# HB-OU-MP3-LED_V1_3.net
KiCad netlist of a schematic drawn in EAGLE
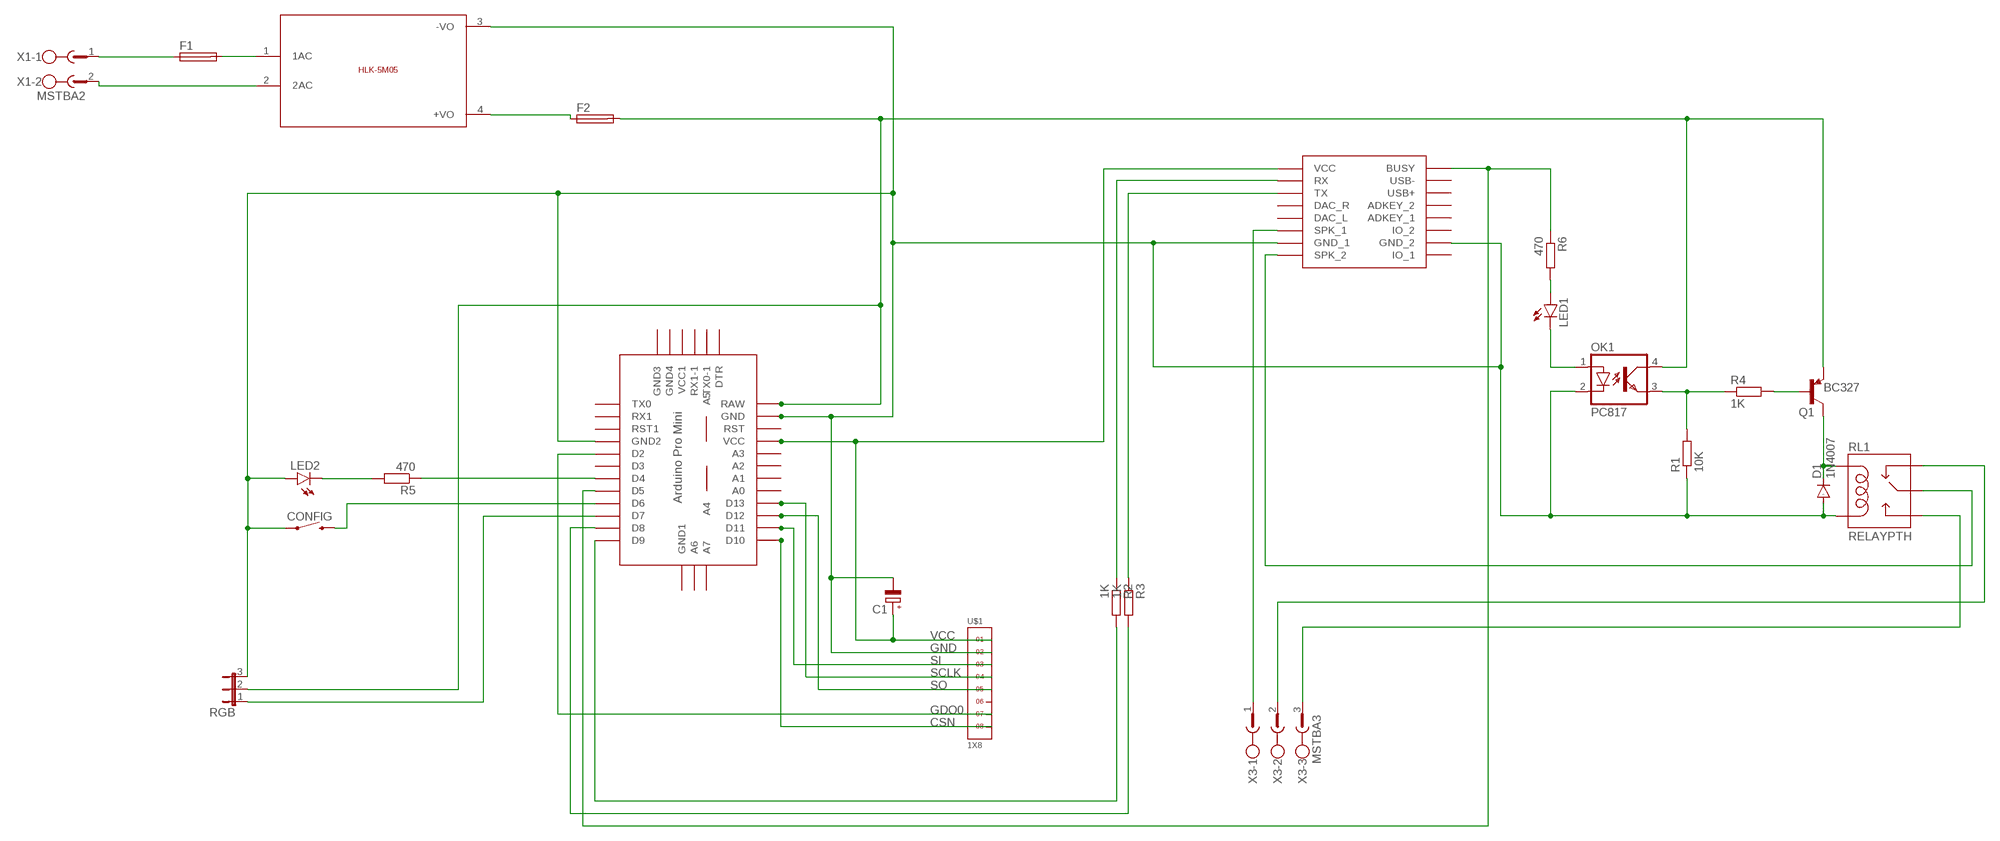
[diagram p0: schematic, sheet 1]

(export (version "E")
  (design (tool "Eeschema 10.0.6"))
  (components
    (comp (ref "C1")
      (value "CPOL-EUE2.5-5")
      (footprint "eagle-import:E2,5-5")
      (libsource (lib "eagle-import") (part "CPOL-EUE2.5-5"))
    )
    (comp (ref "CONFIG")
      (value "MOMENTARY-SWITCH-SPST-PTH-6.0MM-KIT")
      (footprint "eagle-import:TACTILE_SWITCH_PTH_6.0MM_KIT")
      (libsource (lib "eagle-import") (part "MOMENTARY-SWITCH-SPST-PTH-6.0MM-KIT"))
    )
    (comp (ref "D1")
      (value "1N4007")
      (footprint "eagle-import:DO41-10")
      (libsource (lib "eagle-import") (part "1N4004"))
    )
    (comp (ref "F1")
      (value "SH22,5A")
      (footprint "eagle-import:SH22,5A")
      (fields (field (name "MPN") "0031.7701.11"))
      (libsource (lib "eagle-import") (part "SH22,5A"))
    )
    (comp (ref "F2")
      (value "SH22,5A")
      (footprint "eagle-import:SH22,5A")
      (fields (field (name "MPN") "0031.7701.11"))
      (libsource (lib "eagle-import") (part "SH22,5A"))
    )
    (comp (ref "LED1")
      (value "LED3MM")
      (footprint "eagle-import:LED3MM")
      (libsource (lib "eagle-import") (part "LED3MM"))
    )
    (comp (ref "LED2")
      (value "LED3MM")
      (footprint "eagle-import:LED3MM")
      (libsource (lib "eagle-import") (part "LED3MM"))
    )
    (comp (ref "OK1")
      (value "PC817")
      (footprint "eagle-import:DIL04")
      (fields (field (name "MPN") "PC817X4J000F"))
      (libsource (lib "eagle-import") (part "PC817"))
    )
    (comp (ref "Q1")
      (value "BC327")
      (footprint "eagle-import:TO92")
      (libsource (lib "eagle-import") (part "BC327"))
    )
    (comp (ref "R1")
      (value "10K")
      (footprint "eagle-import:0309_10")
      (libsource (lib "eagle-import") (part "R-EU_0309/10"))
    )
    (comp (ref "R2")
      (value "1K")
      (footprint "eagle-import:0309_10")
      (libsource (lib "eagle-import") (part "R-EU_0309/10"))
    )
    (comp (ref "R3")
      (value "1K")
      (footprint "eagle-import:0309_10")
      (libsource (lib "eagle-import") (part "R-EU_0309/10"))
    )
    (comp (ref "R4")
      (value "1K")
      (footprint "eagle-import:0309_10")
      (libsource (lib "eagle-import") (part "R-EU_0309/10"))
    )
    (comp (ref "R5")
      (value "470")
      (footprint "eagle-import:0309_10")
      (libsource (lib "eagle-import") (part "R-EU_0309/10"))
    )
    (comp (ref "R6")
      (value "470")
      (footprint "eagle-import:0309_10")
      (libsource (lib "eagle-import") (part "R-EU_0309/10"))
    )
    (comp (ref "RGB")
      (value "JP2E")
      (footprint "eagle-import:JP2")
      (libsource (lib "eagle-import") (part "JP2E"))
    )
    (comp (ref "RL1")
      (value "RELAYPTH")
      (footprint "eagle-import:SRD-05VDC-SL-C")
      (libsource (lib "eagle-import") (part "RELAYPTH"))
    )
    (comp (ref "U$1")
      (value "1X8")
      (footprint "eagle-import:1X8")
      (libsource (lib "eagle-import") (part "1X8"))
    )
    (comp (ref "U$2")
      (value "ABK-PRO-MINI")
      (footprint "eagle-import:ABK-PRO-MINI")
      (libsource (lib "eagle-import") (part "ABK-PRO-MINI"))
    )
    (comp (ref "U$3")
      (value "5VDC/5W")
      (footprint "eagle-import:HLK-5M05")
      (libsource (lib "eagle-import") (part "HLK-5M05"))
    )
    (comp (ref "U$4")
      (value "DFPLAYER")
      (footprint "eagle-import:DFPLAYER")
      (libsource (lib "eagle-import") (part "DFPLAYER"))
    )
    (comp (ref "X1")
      (value "MSTBA2")
      (footprint "eagle-import:MSTBA2")
      (fields (field (name "MF") "FARNELL") (field (name "MPN") "1757242"))
      (libsource (lib "eagle-import") (part "MSTBA2"))
    )
    (comp (ref "X3")
      (value "MSTBA3")
      (footprint "eagle-import:MSTBA3")
      (fields (field (name "MF") "FARNELL") (field (name "MPN") "1757255"))
      (libsource (lib "eagle-import") (part "MSTBA3"))
    )
  )
  (nets
    (net (code "1") (name "/CSN") (class "Default")
      (node (ref "U$1") (pin "8") (pinfunction "8_8") (pintype "bidirectional"))
      (node (ref "U$2") (pin "D10") (pinfunction "D10_D10") (pintype "bidirectional"))
    )
    (net (code "2") (name "/GDO0") (class "Default")
      (node (ref "U$1") (pin "7") (pinfunction "7_7") (pintype "bidirectional"))
      (node (ref "U$2") (pin "D2") (pinfunction "D2_D2") (pintype "bidirectional"))
    )
    (net (code "3") (name "/GND") (class "Default")
      (node (ref "C1") (pin "-") (pinfunction "-_-") (pintype "passive"))
      (node (ref "CONFIG") (pin "1") (pinfunction "1_1") (pintype "passive"))
      (node (ref "D1") (pin "A") (pinfunction "A_A") (pintype "passive"))
      (node (ref "LED2") (pin "A") (pinfunction "A_A") (pintype "passive"))
      (node (ref "OK1") (pin "2") (pinfunction "C_2") (pintype "passive"))
      (node (ref "R1") (pin "1") (pinfunction "1_1") (pintype "passive"))
      (node (ref "RGB") (pin "3") (pinfunction "3_3") (pintype "passive"))
      (node (ref "RL1") (pin "COIL0") (pinfunction "COIL0_COIL0") (pintype "bidirectional"))
      (node (ref "U$1") (pin "2") (pinfunction "2_2") (pintype "bidirectional"))
      (node (ref "U$2") (pin "GND") (pinfunction "GND_GND") (pintype "bidirectional"))
      (node (ref "U$2") (pin "GND1") (pinfunction "GND2_GND1") (pintype "bidirectional"))
      (node (ref "U$3") (pin "3") (pinfunction "-VO_3") (pintype "bidirectional"))
      (node (ref "U$4") (pin "GND_1") (pinfunction "GND_1_GND_1") (pintype "bidirectional"))
      (node (ref "U$4") (pin "GND_2") (pinfunction "GND_2_GND_2") (pintype "bidirectional"))
    )
    (net (code "4") (name "/SCLK") (class "Default")
      (node (ref "U$1") (pin "4") (pinfunction "4_4") (pintype "bidirectional"))
      (node (ref "U$2") (pin "D13") (pinfunction "D13_D13") (pintype "bidirectional"))
    )
    (net (code "5") (name "/SI") (class "Default")
      (node (ref "U$1") (pin "3") (pinfunction "3_3") (pintype "bidirectional"))
      (node (ref "U$2") (pin "D11") (pinfunction "D11_D11") (pintype "bidirectional"))
    )
    (net (code "6") (name "/SO") (class "Default")
      (node (ref "U$1") (pin "5") (pinfunction "5_5") (pintype "bidirectional"))
      (node (ref "U$2") (pin "D12") (pinfunction "D12_D12") (pintype "bidirectional"))
    )
    (net (code "7") (name "/VCC") (class "Default")
      (node (ref "C1") (pin "+") (pinfunction "+_+") (pintype "passive"))
      (node (ref "U$1") (pin "1") (pinfunction "1_1") (pintype "bidirectional"))
      (node (ref "U$2") (pin "VCC") (pinfunction "VCC_VCC") (pintype "bidirectional"))
      (node (ref "U$4") (pin "VCC") (pinfunction "VCC_VCC") (pintype "bidirectional"))
    )
    (net (code "8") (name "Net-(CONFIG-2)") (class "Default")
      (node (ref "CONFIG") (pin "3") (pinfunction "2_3") (pintype "passive"))
      (node (ref "U$2") (pin "D6") (pinfunction "D6_D6") (pintype "bidirectional"))
    )
    (net (code "9") (name "Net-(F1-Pad1)") (class "Default")
      (node (ref "F1") (pin "1") (pinfunction "1_1") (pintype "passive"))
      (node (ref "X1") (pin "1") (pinfunction "1_1") (pintype "passive"))
    )
    (net (code "10") (name "Net-(LED1-C)") (class "Default")
      (node (ref "LED1") (pin "K") (pinfunction "C_K") (pintype "passive"))
      (node (ref "OK1") (pin "1") (pinfunction "A_1") (pintype "passive"))
    )
    (net (code "11") (name "Net-(LED1-PadA)") (class "Default")
      (node (ref "LED1") (pin "A") (pinfunction "A_A") (pintype "passive"))
      (node (ref "R6") (pin "2") (pinfunction "2_2") (pintype "passive"))
    )
    (net (code "12") (name "Net-(LED2-C)") (class "Default")
      (node (ref "LED2") (pin "K") (pinfunction "C_K") (pintype "passive"))
      (node (ref "R5") (pin "2") (pinfunction "2_2") (pintype "passive"))
    )
    (net (code "13") (name "Net-(OK1-COL)") (class "Default")
      (node (ref "F2") (pin "2") (pinfunction "2_2") (pintype "passive"))
      (node (ref "OK1") (pin "4") (pinfunction "COL_4") (pintype "passive"))
      (node (ref "Q1") (pin "1") (pinfunction "E_1") (pintype "passive"))
      (node (ref "RGB") (pin "2") (pinfunction "2_2") (pintype "passive"))
      (node (ref "U$2") (pin "RAW") (pinfunction "RAW_RAW") (pintype "bidirectional"))
    )
    (net (code "14") (name "Net-(OK1-EMIT)") (class "Default")
      (node (ref "OK1") (pin "3") (pinfunction "EMIT_3") (pintype "passive"))
      (node (ref "R1") (pin "2") (pinfunction "2_2") (pintype "passive"))
      (node (ref "R4") (pin "1") (pinfunction "1_1") (pintype "passive"))
    )
    (net (code "15") (name "Net-(Q1-B)") (class "Default")
      (node (ref "Q1") (pin "2") (pinfunction "B_2") (pintype "passive"))
      (node (ref "R4") (pin "2") (pinfunction "2_2") (pintype "passive"))
    )
    (net (code "16") (name "Net-(Q1-C)") (class "Default")
      (node (ref "D1") (pin "C") (pinfunction "C_C") (pintype "passive"))
      (node (ref "Q1") (pin "3") (pinfunction "C_3") (pintype "passive"))
      (node (ref "RL1") (pin "COIL1") (pinfunction "COIL1_COIL1") (pintype "bidirectional"))
    )
    (net (code "17") (name "Net-(R2-Pad1)") (class "Default")
      (node (ref "R2") (pin "1") (pinfunction "1_1") (pintype "passive"))
      (node (ref "U$4") (pin "RX") (pinfunction "RX_RX") (pintype "bidirectional"))
    )
    (net (code "18") (name "Net-(R2-Pad2)") (class "Default")
      (node (ref "R2") (pin "2") (pinfunction "2_2") (pintype "passive"))
      (node (ref "U$2") (pin "D9") (pinfunction "D9_D9") (pintype "bidirectional"))
    )
    (net (code "19") (name "Net-(R3-Pad1)") (class "Default")
      (node (ref "R3") (pin "1") (pinfunction "1_1") (pintype "passive"))
      (node (ref "U$4") (pin "TX") (pinfunction "TX_TX") (pintype "bidirectional"))
    )
    (net (code "20") (name "Net-(R3-Pad2)") (class "Default")
      (node (ref "R3") (pin "2") (pinfunction "2_2") (pintype "passive"))
      (node (ref "U$2") (pin "D8") (pinfunction "D8_D8") (pintype "bidirectional"))
    )
    (net (code "21") (name "Net-(R5-Pad1)") (class "Default")
      (node (ref "R5") (pin "1") (pinfunction "1_1") (pintype "passive"))
      (node (ref "U$2") (pin "D4") (pinfunction "D4_D4") (pintype "bidirectional"))
    )
    (net (code "22") (name "Net-(R6-Pad1)") (class "Default")
      (node (ref "R6") (pin "1") (pinfunction "1_1") (pintype "passive"))
      (node (ref "U$2") (pin "D5") (pinfunction "D5_D5") (pintype "bidirectional"))
      (node (ref "U$4") (pin "BUSY") (pinfunction "BUSY_BUSY") (pintype "bidirectional"))
    )
    (net (code "23") (name "Net-(RGB-Pad1)") (class "Default")
      (node (ref "RGB") (pin "1") (pinfunction "1_1") (pintype "passive"))
      (node (ref "U$2") (pin "D7") (pinfunction "D7_D7") (pintype "bidirectional"))
    )
    (net (code "24") (name "Net-(RL1-SWCLOSE)") (class "Default")
      (node (ref "RL1") (pin "SWCLOSED") (pinfunction "SWCLOSE_SWCLOSED") (pintype "bidirectional"))
      (node (ref "X3") (pin "2") (pinfunction "1_2") (pintype "passive"))
    )
    (net (code "25") (name "Net-(U$3-+VO)") (class "Default")
      (node (ref "F2") (pin "1") (pinfunction "1_1") (pintype "passive"))
      (node (ref "U$3") (pin "4") (pinfunction "+VO_4") (pintype "bidirectional"))
    )
    (net (code "26") (name "Net-(U$3-1AC)") (class "Default")
      (node (ref "F1") (pin "2") (pinfunction "2_2") (pintype "passive"))
      (node (ref "U$3") (pin "1") (pinfunction "1AC_1") (pintype "bidirectional"))
    )
    (net (code "27") (name "Net-(U$3-2AC)") (class "Default")
      (node (ref "U$3") (pin "2") (pinfunction "2AC_2") (pintype "bidirectional"))
      (node (ref "X1") (pin "2") (pinfunction "1_2") (pintype "passive"))
    )
    (net (code "28") (name "Net-(U$4-SPK_1)") (class "Default")
      (node (ref "U$4") (pin "SPK1") (pinfunction "SPK_1_SPK1") (pintype "bidirectional"))
      (node (ref "X3") (pin "1") (pinfunction "1_1") (pintype "passive"))
    )
    (net (code "29") (name "Net-(U$4-SPK_2)") (class "Default")
      (node (ref "RL1") (pin "SWCOMMON") (pinfunction "SWCOMMON_SWCOMMON") (pintype "bidirectional"))
      (node (ref "U$4") (pin "SPK2") (pinfunction "SPK_2_SPK2") (pintype "bidirectional"))
    )
    (net (code "30") (name "Net-(X3C-1)") (class "Default")
      (node (ref "RL1") (pin "SWOPEN") (pinfunction "SWOPEN_SWOPEN") (pintype "bidirectional"))
      (node (ref "X3") (pin "3") (pinfunction "1_3") (pintype "passive"))
    )
    (net (code "31") (name "unconnected-(U$1-Pad6)") (class "Default")
      (node (ref "U$1") (pin "6") (pinfunction "6_6") (pintype "bidirectional"))
    )
    (net (code "32") (name "unconnected-(U$2-GND1-PadGND4)") (class "Default")
      (node (ref "U$2") (pin "GND4") (pinfunction "GND1_GND4") (pintype "bidirectional"))
    )
    (net (code "33") (name "unconnected-(U$2-GND3-PadGND2)") (class "Default")
      (node (ref "U$2") (pin "GND2") (pinfunction "GND3_GND2") (pintype "bidirectional"))
    )
    (net (code "34") (name "unconnected-(U$2-GND4-PadGND3)") (class "Default")
      (node (ref "U$2") (pin "GND3") (pinfunction "GND4_GND3") (pintype "bidirectional"))
    )
    (net (code "35") (name "unconnected-(U$2-PadA0)") (class "Default")
      (node (ref "U$2") (pin "A0") (pinfunction "A0_A0") (pintype "bidirectional"))
    )
    (net (code "36") (name "unconnected-(U$2-PadA1)") (class "Default")
      (node (ref "U$2") (pin "A1") (pinfunction "A1_A1") (pintype "bidirectional"))
    )
    (net (code "37") (name "unconnected-(U$2-PadA2)") (class "Default")
      (node (ref "U$2") (pin "A2") (pinfunction "A2_A2") (pintype "bidirectional"))
    )
    (net (code "38") (name "unconnected-(U$2-PadA3)") (class "Default")
      (node (ref "U$2") (pin "A3") (pinfunction "A3_A3") (pintype "bidirectional"))
    )
    (net (code "39") (name "unconnected-(U$2-PadA4)") (class "Default")
      (node (ref "U$2") (pin "A4") (pinfunction "A4_A4") (pintype "bidirectional"))
    )
    (net (code "40") (name "unconnected-(U$2-PadA5)") (class "Default")
      (node (ref "U$2") (pin "A5") (pinfunction "A5_A5") (pintype "bidirectional"))
    )
    (net (code "41") (name "unconnected-(U$2-PadA6)") (class "Default")
      (node (ref "U$2") (pin "A6") (pinfunction "A6_A6") (pintype "bidirectional"))
    )
    (net (code "42") (name "unconnected-(U$2-PadA7)") (class "Default")
      (node (ref "U$2") (pin "A7") (pinfunction "A7_A7") (pintype "bidirectional"))
    )
    (net (code "43") (name "unconnected-(U$2-PadD3)") (class "Default")
      (node (ref "U$2") (pin "D3") (pinfunction "D3_D3") (pintype "bidirectional"))
    )
    (net (code "44") (name "unconnected-(U$2-PadDTR)") (class "Default")
      (node (ref "U$2") (pin "DTR") (pinfunction "DTR_DTR") (pintype "bidirectional"))
    )
    (net (code "45") (name "unconnected-(U$2-PadRST)") (class "Default")
      (node (ref "U$2") (pin "RST") (pinfunction "RST_RST") (pintype "bidirectional"))
    )
    (net (code "46") (name "unconnected-(U$2-PadRST1)") (class "Default")
      (node (ref "U$2") (pin "RST1") (pinfunction "RST1_RST1") (pintype "bidirectional"))
    )
    (net (code "47") (name "unconnected-(U$2-PadRX1)") (class "Default")
      (node (ref "U$2") (pin "RX1") (pinfunction "RX1_RX1") (pintype "bidirectional"))
    )
    (net (code "48") (name "unconnected-(U$2-PadRX1-1)") (class "Default")
      (node (ref "U$2") (pin "RX1-1") (pinfunction "RX1-1_RX1-1") (pintype "bidirectional"))
    )
    (net (code "49") (name "unconnected-(U$2-PadTX0)") (class "Default")
      (node (ref "U$2") (pin "TX0") (pinfunction "TX0_TX0") (pintype "bidirectional"))
    )
    (net (code "50") (name "unconnected-(U$2-PadTX0-1)") (class "Default")
      (node (ref "U$2") (pin "TX0-1") (pinfunction "TX0-1_TX0-1") (pintype "bidirectional"))
    )
    (net (code "51") (name "unconnected-(U$2-PadVCC1)") (class "Default")
      (node (ref "U$2") (pin "VCC1") (pinfunction "VCC1_VCC1") (pintype "bidirectional"))
    )
    (net (code "52") (name "unconnected-(U$4-ADKEY_1-PadADKEY1)") (class "Default")
      (node (ref "U$4") (pin "ADKEY1") (pinfunction "ADKEY_1_ADKEY1") (pintype "bidirectional"))
    )
    (net (code "53") (name "unconnected-(U$4-ADKEY_2-PadADKEY2)") (class "Default")
      (node (ref "U$4") (pin "ADKEY2") (pinfunction "ADKEY_2_ADKEY2") (pintype "bidirectional"))
    )
    (net (code "54") (name "unconnected-(U$4-IO_1-PadIO1)") (class "Default")
      (node (ref "U$4") (pin "IO1") (pinfunction "IO_1_IO1") (pintype "bidirectional"))
    )
    (net (code "55") (name "unconnected-(U$4-IO_2-PadIO2)") (class "Default")
      (node (ref "U$4") (pin "IO2") (pinfunction "IO_2_IO2") (pintype "bidirectional"))
    )
    (net (code "56") (name "unconnected-(U$4-PadDAC_L)") (class "Default")
      (node (ref "U$4") (pin "DAC_L") (pinfunction "DAC_L_DAC_L") (pintype "bidirectional"))
    )
    (net (code "57") (name "unconnected-(U$4-PadDAC_R)") (class "Default")
      (node (ref "U$4") (pin "DAC_R") (pinfunction "DAC_R_DAC_R") (pintype "bidirectional"))
    )
    (net (code "58") (name "unconnected-(U$4-PadUSB+)") (class "Default")
      (node (ref "U$4") (pin "USB+") (pinfunction "USB+_USB+") (pintype "bidirectional"))
    )
    (net (code "59") (name "unconnected-(U$4-PadUSB-)") (class "Default")
      (node (ref "U$4") (pin "USB-") (pinfunction "USB-_USB-") (pintype "bidirectional"))
    )
  )
)
